# MCU.net
KiCad netlist of a schematic drawn in Altium Designer
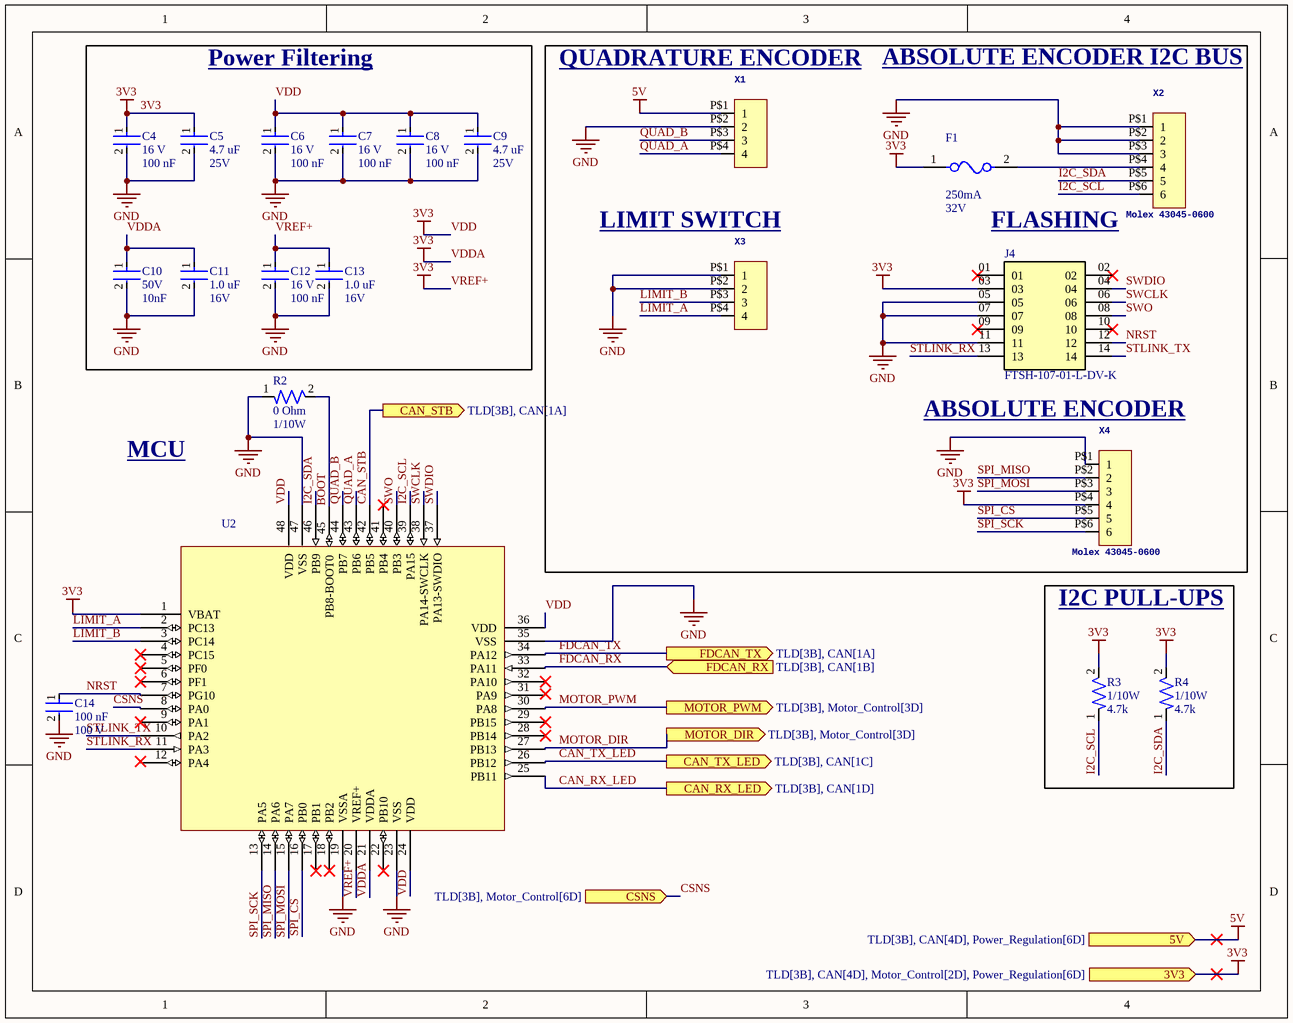
[diagram p0: MCU.SchDoc]

(export (version "E")
  (design (tool "Eeschema 10.0.6"))
  (components
    (comp (ref "C4")
      (value "CC0402KRX7R7BB104")
      (footprint "CAP-0402")
      (description "CAP CER 0.1UF 16V X7R 0402")
      (fields (field (name "VOLTAGE RATING") "16 V") (field (name "CAPACITANCE") "100 nF"))
      (libsource (lib "JLC_25") (part "CAP-0.1U-0001"))
    )
    (comp (ref "C5")
      (value "CC0603KRX5R8BB475")
      (footprint "CAP-0603")
      (description "CAP CER 4.7UF 25V X5R 0603")
      (fields (field (name "CAPACITANCE") "4.7 uF") (field (name "VOLTAGE") "25V"))
      (libsource (lib "JLC_25") (part "CAP-4.7U-0001"))
    )
    (comp (ref "C6")
      (value "CC0402KRX7R7BB104")
      (footprint "CAP-0402")
      (description "CAP CER 0.1UF 16V X7R 0402")
      (fields (field (name "VOLTAGE RATING") "16 V") (field (name "CAPACITANCE") "100 nF"))
      (libsource (lib "JLC_25") (part "CAP-0.1U-0001"))
    )
    (comp (ref "C7")
      (value "CC0402KRX7R7BB104")
      (footprint "CAP-0402")
      (description "CAP CER 0.1UF 16V X7R 0402")
      (fields (field (name "VOLTAGE RATING") "16 V") (field (name "CAPACITANCE") "100 nF"))
      (libsource (lib "JLC_25") (part "CAP-0.1U-0001"))
    )
    (comp (ref "C8")
      (value "CC0402KRX7R7BB104")
      (footprint "CAP-0402")
      (description "CAP CER 0.1UF 16V X7R 0402")
      (fields (field (name "VOLTAGE RATING") "16 V") (field (name "CAPACITANCE") "100 nF"))
      (libsource (lib "JLC_25") (part "CAP-0.1U-0001"))
    )
    (comp (ref "C9")
      (value "CC0603KRX5R8BB475")
      (footprint "CAP-0603")
      (description "CAP CER 4.7UF 25V X5R 0603")
      (fields (field (name "CAPACITANCE") "4.7 uF") (field (name "VOLTAGE") "25V"))
      (libsource (lib "JLC_25") (part "CAP-4.7U-0001"))
    )
    (comp (ref "C10")
      (value "GRM2195C1H103JA01D")
      (footprint "CAP-0805")
      (description "CAP CER 10000PF 50V C0G/NP0 0805")
      (fields (field (name "VOLTAGE") "50V") (field (name "CAPACITANCE") "10nF"))
      (libsource (lib "JLC_25") (part "CAP-10N-0001"))
    )
    (comp (ref "C11")
      (value "CC0603KRX7R7BB105")
      (footprint "CAP-0603")
      (description "CAP CER 1UF 16V X7R 0603")
      (fields (field (name "CAPACITANCE") "1.0 uF") (field (name "VOLTAGE") "16V"))
      (libsource (lib "JLC_25") (part "CAP-1U-0002"))
    )
    (comp (ref "C12")
      (value "CC0402KRX7R7BB104")
      (footprint "CAP-0402")
      (description "CAP CER 0.1UF 16V X7R 0402")
      (fields (field (name "VOLTAGE RATING") "16 V") (field (name "CAPACITANCE") "100 nF"))
      (libsource (lib "JLC_25") (part "CAP-0.1U-0001"))
    )
    (comp (ref "C13")
      (value "CC0603KRX7R7BB105")
      (footprint "CAP-0603")
      (description "CAP CER 1UF 16V X7R 0603")
      (fields (field (name "CAPACITANCE") "1.0 uF") (field (name "VOLTAGE") "16V"))
      (libsource (lib "JLC_25") (part "CAP-1U-0002"))
    )
    (comp (ref "C14")
      (value "CC0603KRX7R0BB104")
      (footprint "CAP-0603")
      (description "CAP CER 0.1UF 100V X7R 0603")
      (fields (field (name "CAPACITANCE") "100 nF") (field (name "VOLTAGE") "100 V"))
      (libsource (lib "JLC_25") (part "CAP-100N-0001"))
    )
    (comp (ref "F1")
      (value "0467.250NRHF")
      (footprint "RES-0603")
      (description "FUSE BRD MT 250MA 32VAC 32VDC")
      (fields (field (name "FUSE CURRENT") "250mA") (field (name "VOLTAGE RATING") "32V"))
      (libsource (lib "JLC_25") (part "FUSE-0002"))
    )
    (comp (ref "J4")
      (value "FTSH-107-01-L-DV-K")
      (footprint "SAMTEC_FTSH-107-01-L-DV-K")
      (description "Connector Header Surface Mount 14 position 0.050\" (1.27mm)")
      (fields (field (name "MF") "Samtec"))
      (libsource (lib "MasterLib") (part "CONN_Flashing-0001"))
    )
    (comp (ref "R2")
      (value "RESC1607X60N")
      (footprint "RESC1607X60N")
      (description "0 Ohms Jumper Chip Resistor 0603 (1608 Metric) Moisture Resistant Thick Film")
      (fields
        (field (name "JLC PART NUMBER") "C106231")
        (field (name "RESISTANCE") "0 Ohm")
        (field (name "POWER") "1/10W")
      )
      (libsource (lib "MasterLib") (part "RES-0-0003"))
    )
    (comp (ref "R3")
      (value "RC0603FR-074K7L")
      (footprint "RES-0603")
      (description "RES 4.7K OHM 1% 1/10W 0603")
      (fields
        (field (name "TOLERANCE") "1%")
        (field (name "POWER") "1/10W")
        (field (name "RESISTANCE") "4.7k")
      )
      (libsource (lib "JLC_25") (part "RES-4.7k-0001"))
    )
    (comp (ref "R4")
      (value "RC0603FR-074K7L")
      (footprint "RES-0603")
      (description "RES 4.7K OHM 1% 1/10W 0603")
      (fields
        (field (name "TOLERANCE") "1%")
        (field (name "POWER") "1/10W")
        (field (name "RESISTANCE") "4.7k")
      )
      (libsource (lib "JLC_25") (part "RES-4.7k-0001"))
    )
    (comp (ref "U2")
      (value "STM32G431CBT6")
      (footprint "IC-LQFP48")
      (description "IC MCU 32BIT 128KB FLASH 48LQFP")
      (libsource (lib "JLC_25") (part "IC-STM32G431CBT6"))
    )
    (comp (ref "X1")
      (value "Molex - Micro-Fit 3.0 Series connector,  3.00mm (0.118\") pitch header, 4 positions.")
      (footprint "43045-0400")
      (libsource (lib "Molex Microfit") (part "HEADER_POS4_?43045-0401"))
    )
    (comp (ref "X2")
      (value "Molex 43045-0600")
      (footprint "43045-0600")
      (libsource (lib "Molex Microfit") (part "Micro-Fit Molex 6 Pin 2 Row Right Angle"))
    )
    (comp (ref "X3")
      (value "Molex - Micro-Fit 3.0 Series connector,  3.00mm (0.118\") pitch header, 4 positions.")
      (footprint "43045-0400")
      (libsource (lib "Molex Microfit") (part "HEADER_POS4_?43045-0401"))
    )
    (comp (ref "X4")
      (value "Molex 43045-0600")
      (footprint "43045-0600")
      (libsource (lib "Molex Microfit") (part "Micro-Fit Molex 6 Pin 2 Row Right Angle"))
    )
  )
  (nets
    (net (code "1") (name "/BOOT") (class "Default")
      (node (ref "R2") (pin "2") (pinfunction "2_2") (pintype "passive"))
      (node (ref "U2") (pin "45") (pinfunction "PB8-BOOT0_45") (pintype "bidirectional"))
    )
    (net (code "2") (name "/CAN_RX_LED") (class "Default")
      (node (ref "U2") (pin "25") (pinfunction "PB11_25") (pintype "output"))
    )
    (net (code "3") (name "/CAN_STB") (class "Default")
      (node (ref "U2") (pin "42") (pinfunction "PB5_42") (pintype "bidirectional"))
    )
    (net (code "4") (name "/CAN_TX_LED") (class "Default")
      (node (ref "U2") (pin "26") (pinfunction "PB12_26") (pintype "output"))
    )
    (net (code "5") (name "/CSNS") (class "Default")
      (node (ref "U2") (pin "8") (pinfunction "PA0_8") (pintype "bidirectional"))
    )
    (net (code "6") (name "/FDCAN_RX") (class "Default")
      (node (ref "U2") (pin "33") (pinfunction "PA11_33") (pintype "input"))
    )
    (net (code "7") (name "/FDCAN_TX") (class "Default")
      (node (ref "U2") (pin "34") (pinfunction "PA12_34") (pintype "output"))
    )
    (net (code "8") (name "/I2C_SCL") (class "Default")
      (node (ref "R3") (pin "1") (pinfunction "1_1") (pintype "passive"))
      (node (ref "U2") (pin "39") (pinfunction "PA15_39") (pintype "bidirectional"))
      (node (ref "X2") (pin "P$6") (pinfunction "6_P$6") (pintype "passive"))
    )
    (net (code "9") (name "/I2C_SDA") (class "Default")
      (node (ref "R4") (pin "1") (pinfunction "1_1") (pintype "passive"))
      (node (ref "U2") (pin "46") (pinfunction "PB9_46") (pintype "input"))
      (node (ref "X2") (pin "P$5") (pinfunction "5_P$5") (pintype "passive"))
    )
    (net (code "10") (name "/LIMIT_A") (class "Default")
      (node (ref "U2") (pin "2") (pinfunction "PC13_2") (pintype "bidirectional"))
      (node (ref "X3") (pin "P$4") (pinfunction "4_P$4") (pintype "passive"))
    )
    (net (code "11") (name "/LIMIT_B") (class "Default")
      (node (ref "U2") (pin "3") (pinfunction "PC14_3") (pintype "bidirectional"))
      (node (ref "X3") (pin "P$3") (pinfunction "3_P$3") (pintype "passive"))
    )
    (net (code "12") (name "/MOTOR_DIR") (class "Default")
      (node (ref "U2") (pin "27") (pinfunction "PB13_27") (pintype "output"))
    )
    (net (code "13") (name "/MOTOR_PWM") (class "Default")
      (node (ref "U2") (pin "30") (pinfunction "PA8_30") (pintype "output"))
    )
    (net (code "14") (name "/NRST") (class "Default")
      (node (ref "C14") (pin "1") (pinfunction "1_1") (pintype "passive"))
      (node (ref "J4") (pin "12") (pinfunction "12_12") (pintype "passive"))
      (node (ref "U2") (pin "7") (pinfunction "PG10_7") (pintype "bidirectional"))
    )
    (net (code "15") (name "/QUAD_A") (class "Default")
      (node (ref "U2") (pin "43") (pinfunction "PB6_43") (pintype "bidirectional"))
      (node (ref "X1") (pin "P$4") (pinfunction "4_P$4") (pintype "passive"))
    )
    (net (code "16") (name "/QUAD_B") (class "Default")
      (node (ref "U2") (pin "44") (pinfunction "PB7_44") (pintype "bidirectional"))
      (node (ref "X1") (pin "P$3") (pinfunction "3_P$3") (pintype "passive"))
    )
    (net (code "17") (name "/SPI_CS") (class "Default")
      (node (ref "U2") (pin "16") (pinfunction "PB0_16") (pintype "bidirectional"))
      (node (ref "X4") (pin "P$5") (pinfunction "5_P$5") (pintype "passive"))
    )
    (net (code "18") (name "/SPI_MISO") (class "Default")
      (node (ref "U2") (pin "14") (pinfunction "PA6_14") (pintype "bidirectional"))
      (node (ref "X4") (pin "P$2") (pinfunction "2_P$2") (pintype "passive"))
    )
    (net (code "19") (name "/SPI_MOSI") (class "Default")
      (node (ref "U2") (pin "15") (pinfunction "PA7_15") (pintype "bidirectional"))
      (node (ref "X4") (pin "P$3") (pinfunction "3_P$3") (pintype "passive"))
    )
    (net (code "20") (name "/SPI_SCK") (class "Default")
      (node (ref "U2") (pin "13") (pinfunction "PA5_13") (pintype "bidirectional"))
      (node (ref "X4") (pin "P$6") (pinfunction "6_P$6") (pintype "passive"))
    )
    (net (code "21") (name "/STLINK_RX") (class "Default")
      (node (ref "J4") (pin "13") (pinfunction "13_13") (pintype "passive"))
      (node (ref "U2") (pin "11") (pinfunction "PA3_11") (pintype "input"))
    )
    (net (code "22") (name "/STLINK_TX") (class "Default")
      (node (ref "J4") (pin "14") (pinfunction "14_14") (pintype "passive"))
      (node (ref "U2") (pin "10") (pinfunction "PA2_10") (pintype "output"))
    )
    (net (code "23") (name "/SWCLK") (class "Default")
      (node (ref "J4") (pin "06") (pinfunction "06_06") (pintype "passive"))
      (node (ref "U2") (pin "38") (pinfunction "PA14-SWCLK_38") (pintype "input"))
    )
    (net (code "24") (name "/SWDIO") (class "Default")
      (node (ref "J4") (pin "04") (pinfunction "04_04") (pintype "passive"))
      (node (ref "U2") (pin "37") (pinfunction "PA13-SWDIO_37") (pintype "input"))
    )
    (net (code "25") (name "/SWO") (class "Default")
      (node (ref "J4") (pin "08") (pinfunction "08_08") (pintype "passive"))
      (node (ref "U2") (pin "40") (pinfunction "PB3_40") (pintype "bidirectional"))
    )
    (net (code "26") (name "3V3") (class "Default")
      (node (ref "C10") (pin "1") (pinfunction "1_1") (pintype "passive"))
      (node (ref "C11") (pin "1") (pinfunction "1_1") (pintype "passive"))
      (node (ref "C12") (pin "1") (pinfunction "1_1") (pintype "passive"))
      (node (ref "C13") (pin "1") (pinfunction "1_1") (pintype "passive"))
      (node (ref "C4") (pin "1") (pinfunction "1_1") (pintype "passive"))
      (node (ref "C5") (pin "1") (pinfunction "1_1") (pintype "passive"))
      (node (ref "C6") (pin "1") (pinfunction "1_1") (pintype "passive"))
      (node (ref "C7") (pin "1") (pinfunction "1_1") (pintype "passive"))
      (node (ref "C8") (pin "1") (pinfunction "1_1") (pintype "passive"))
      (node (ref "C9") (pin "1") (pinfunction "1_1") (pintype "passive"))
      (node (ref "F1") (pin "1") (pinfunction "1_1") (pintype "passive"))
      (node (ref "J4") (pin "03") (pinfunction "03_03") (pintype "passive"))
      (node (ref "R3") (pin "2") (pinfunction "2_2") (pintype "passive"))
      (node (ref "R4") (pin "2") (pinfunction "2_2") (pintype "passive"))
      (node (ref "U2") (pin "1") (pinfunction "VBAT_1") (pintype "power_in"))
      (node (ref "U2") (pin "20") (pinfunction "VREF+_20") (pintype "power_in"))
      (node (ref "U2") (pin "21") (pinfunction "VDDA_21") (pintype "power_in"))
      (node (ref "U2") (pin "24") (pinfunction "VDD_24") (pintype "power_in"))
      (node (ref "U2") (pin "36") (pinfunction "VDD_36") (pintype "power_in"))
      (node (ref "U2") (pin "48") (pinfunction "VDD_48") (pintype "power_in"))
      (node (ref "X4") (pin "P$4") (pinfunction "4_P$4") (pintype "passive"))
    )
    (net (code "27") (name "5V") (class "Default")
      (node (ref "X1") (pin "P$1") (pinfunction "1_P$1") (pintype "passive"))
    )
    (net (code "28") (name "GND") (class "Default")
      (node (ref "C10") (pin "2") (pinfunction "2_2") (pintype "passive"))
      (node (ref "C11") (pin "2") (pinfunction "2_2") (pintype "passive"))
      (node (ref "C12") (pin "2") (pinfunction "2_2") (pintype "passive"))
      (node (ref "C13") (pin "2") (pinfunction "2_2") (pintype "passive"))
      (node (ref "C14") (pin "2") (pinfunction "2_2") (pintype "passive"))
      (node (ref "C4") (pin "2") (pinfunction "2_2") (pintype "passive"))
      (node (ref "C5") (pin "2") (pinfunction "2_2") (pintype "passive"))
      (node (ref "C6") (pin "2") (pinfunction "2_2") (pintype "passive"))
      (node (ref "C7") (pin "2") (pinfunction "2_2") (pintype "passive"))
      (node (ref "C8") (pin "2") (pinfunction "2_2") (pintype "passive"))
      (node (ref "C9") (pin "2") (pinfunction "2_2") (pintype "passive"))
      (node (ref "J4") (pin "05") (pinfunction "05_05") (pintype "passive"))
      (node (ref "J4") (pin "07") (pinfunction "07_07") (pintype "passive"))
      (node (ref "J4") (pin "11") (pinfunction "11_11") (pintype "passive"))
      (node (ref "R2") (pin "1") (pinfunction "1_1") (pintype "passive"))
      (node (ref "U2") (pin "19") (pinfunction "VSSA_19") (pintype "power_in"))
      (node (ref "U2") (pin "23") (pinfunction "VSS_23") (pintype "power_in"))
      (node (ref "U2") (pin "35") (pinfunction "VSS_35") (pintype "power_in"))
      (node (ref "U2") (pin "47") (pinfunction "VSS_47") (pintype "power_in"))
      (node (ref "X1") (pin "P$2") (pinfunction "2_P$2") (pintype "passive"))
      (node (ref "X2") (pin "P$1") (pinfunction "1_P$1") (pintype "passive"))
      (node (ref "X2") (pin "P$2") (pinfunction "2_P$2") (pintype "passive"))
      (node (ref "X2") (pin "P$3") (pinfunction "3_P$3") (pintype "passive"))
      (node (ref "X3") (pin "P$1") (pinfunction "1_P$1") (pintype "passive"))
      (node (ref "X3") (pin "P$2") (pinfunction "2_P$2") (pintype "passive"))
      (node (ref "X4") (pin "P$1") (pinfunction "1_P$1") (pintype "passive"))
    )
    (net (code "29") (name "Net-(X2-4)") (class "Default")
      (node (ref "F1") (pin "2") (pinfunction "2_2") (pintype "passive"))
      (node (ref "X2") (pin "P$4") (pinfunction "4_P$4") (pintype "passive"))
    )
    (net (code "30") (name "unconnected-(J4-Pad01)") (class "Default")
      (node (ref "J4") (pin "01") (pinfunction "01_01") (pintype "passive+no_connect"))
    )
    (net (code "31") (name "unconnected-(J4-Pad02)") (class "Default")
      (node (ref "J4") (pin "02") (pinfunction "02_02") (pintype "passive+no_connect"))
    )
    (net (code "32") (name "unconnected-(J4-Pad09)") (class "Default")
      (node (ref "J4") (pin "09") (pinfunction "09_09") (pintype "passive+no_connect"))
    )
    (net (code "33") (name "unconnected-(J4-Pad10)") (class "Default")
      (node (ref "J4") (pin "10") (pinfunction "10_10") (pintype "passive+no_connect"))
    )
    (net (code "34") (name "unconnected-(U2-PA1-Pad9)") (class "Default")
      (node (ref "U2") (pin "9") (pinfunction "PA1_9") (pintype "bidirectional+no_connect"))
    )
    (net (code "35") (name "unconnected-(U2-PA4-Pad12)") (class "Default")
      (node (ref "U2") (pin "12") (pinfunction "PA4_12") (pintype "bidirectional"))
    )
    (net (code "36") (name "unconnected-(U2-PA9-Pad31)") (class "Default")
      (node (ref "U2") (pin "31") (pinfunction "PA9_31") (pintype "output"))
    )
    (net (code "37") (name "unconnected-(U2-PA10-Pad32)") (class "Default")
      (node (ref "U2") (pin "32") (pinfunction "PA10_32") (pintype "output+no_connect"))
    )
    (net (code "38") (name "unconnected-(U2-PB1-Pad17)") (class "Default")
      (node (ref "U2") (pin "17") (pinfunction "PB1_17") (pintype "bidirectional+no_connect"))
    )
    (net (code "39") (name "unconnected-(U2-PB2-Pad18)") (class "Default")
      (node (ref "U2") (pin "18") (pinfunction "PB2_18") (pintype "bidirectional+no_connect"))
    )
    (net (code "40") (name "unconnected-(U2-PB4-Pad41)") (class "Default")
      (node (ref "U2") (pin "41") (pinfunction "PB4_41") (pintype "bidirectional+no_connect"))
    )
    (net (code "41") (name "unconnected-(U2-PB10-Pad22)") (class "Default")
      (node (ref "U2") (pin "22") (pinfunction "PB10_22") (pintype "bidirectional+no_connect"))
    )
    (net (code "42") (name "unconnected-(U2-PB14-Pad28)") (class "Default")
      (node (ref "U2") (pin "28") (pinfunction "PB14_28") (pintype "output+no_connect"))
    )
    (net (code "43") (name "unconnected-(U2-PB15-Pad29)") (class "Default")
      (node (ref "U2") (pin "29") (pinfunction "PB15_29") (pintype "output+no_connect"))
    )
    (net (code "44") (name "unconnected-(U2-PC15-Pad4)") (class "Default")
      (node (ref "U2") (pin "4") (pinfunction "PC15_4") (pintype "bidirectional+no_connect"))
    )
    (net (code "45") (name "unconnected-(U2-PF0-Pad5)") (class "Default")
      (node (ref "U2") (pin "5") (pinfunction "PF0_5") (pintype "bidirectional+no_connect"))
    )
    (net (code "46") (name "unconnected-(U2-PF1-Pad6)") (class "Default")
      (node (ref "U2") (pin "6") (pinfunction "PF1_6") (pintype "bidirectional+no_connect"))
    )
  )
)
